# 42Motor_Control.net
KiCad netlist of a schematic drawn in Altium Designer
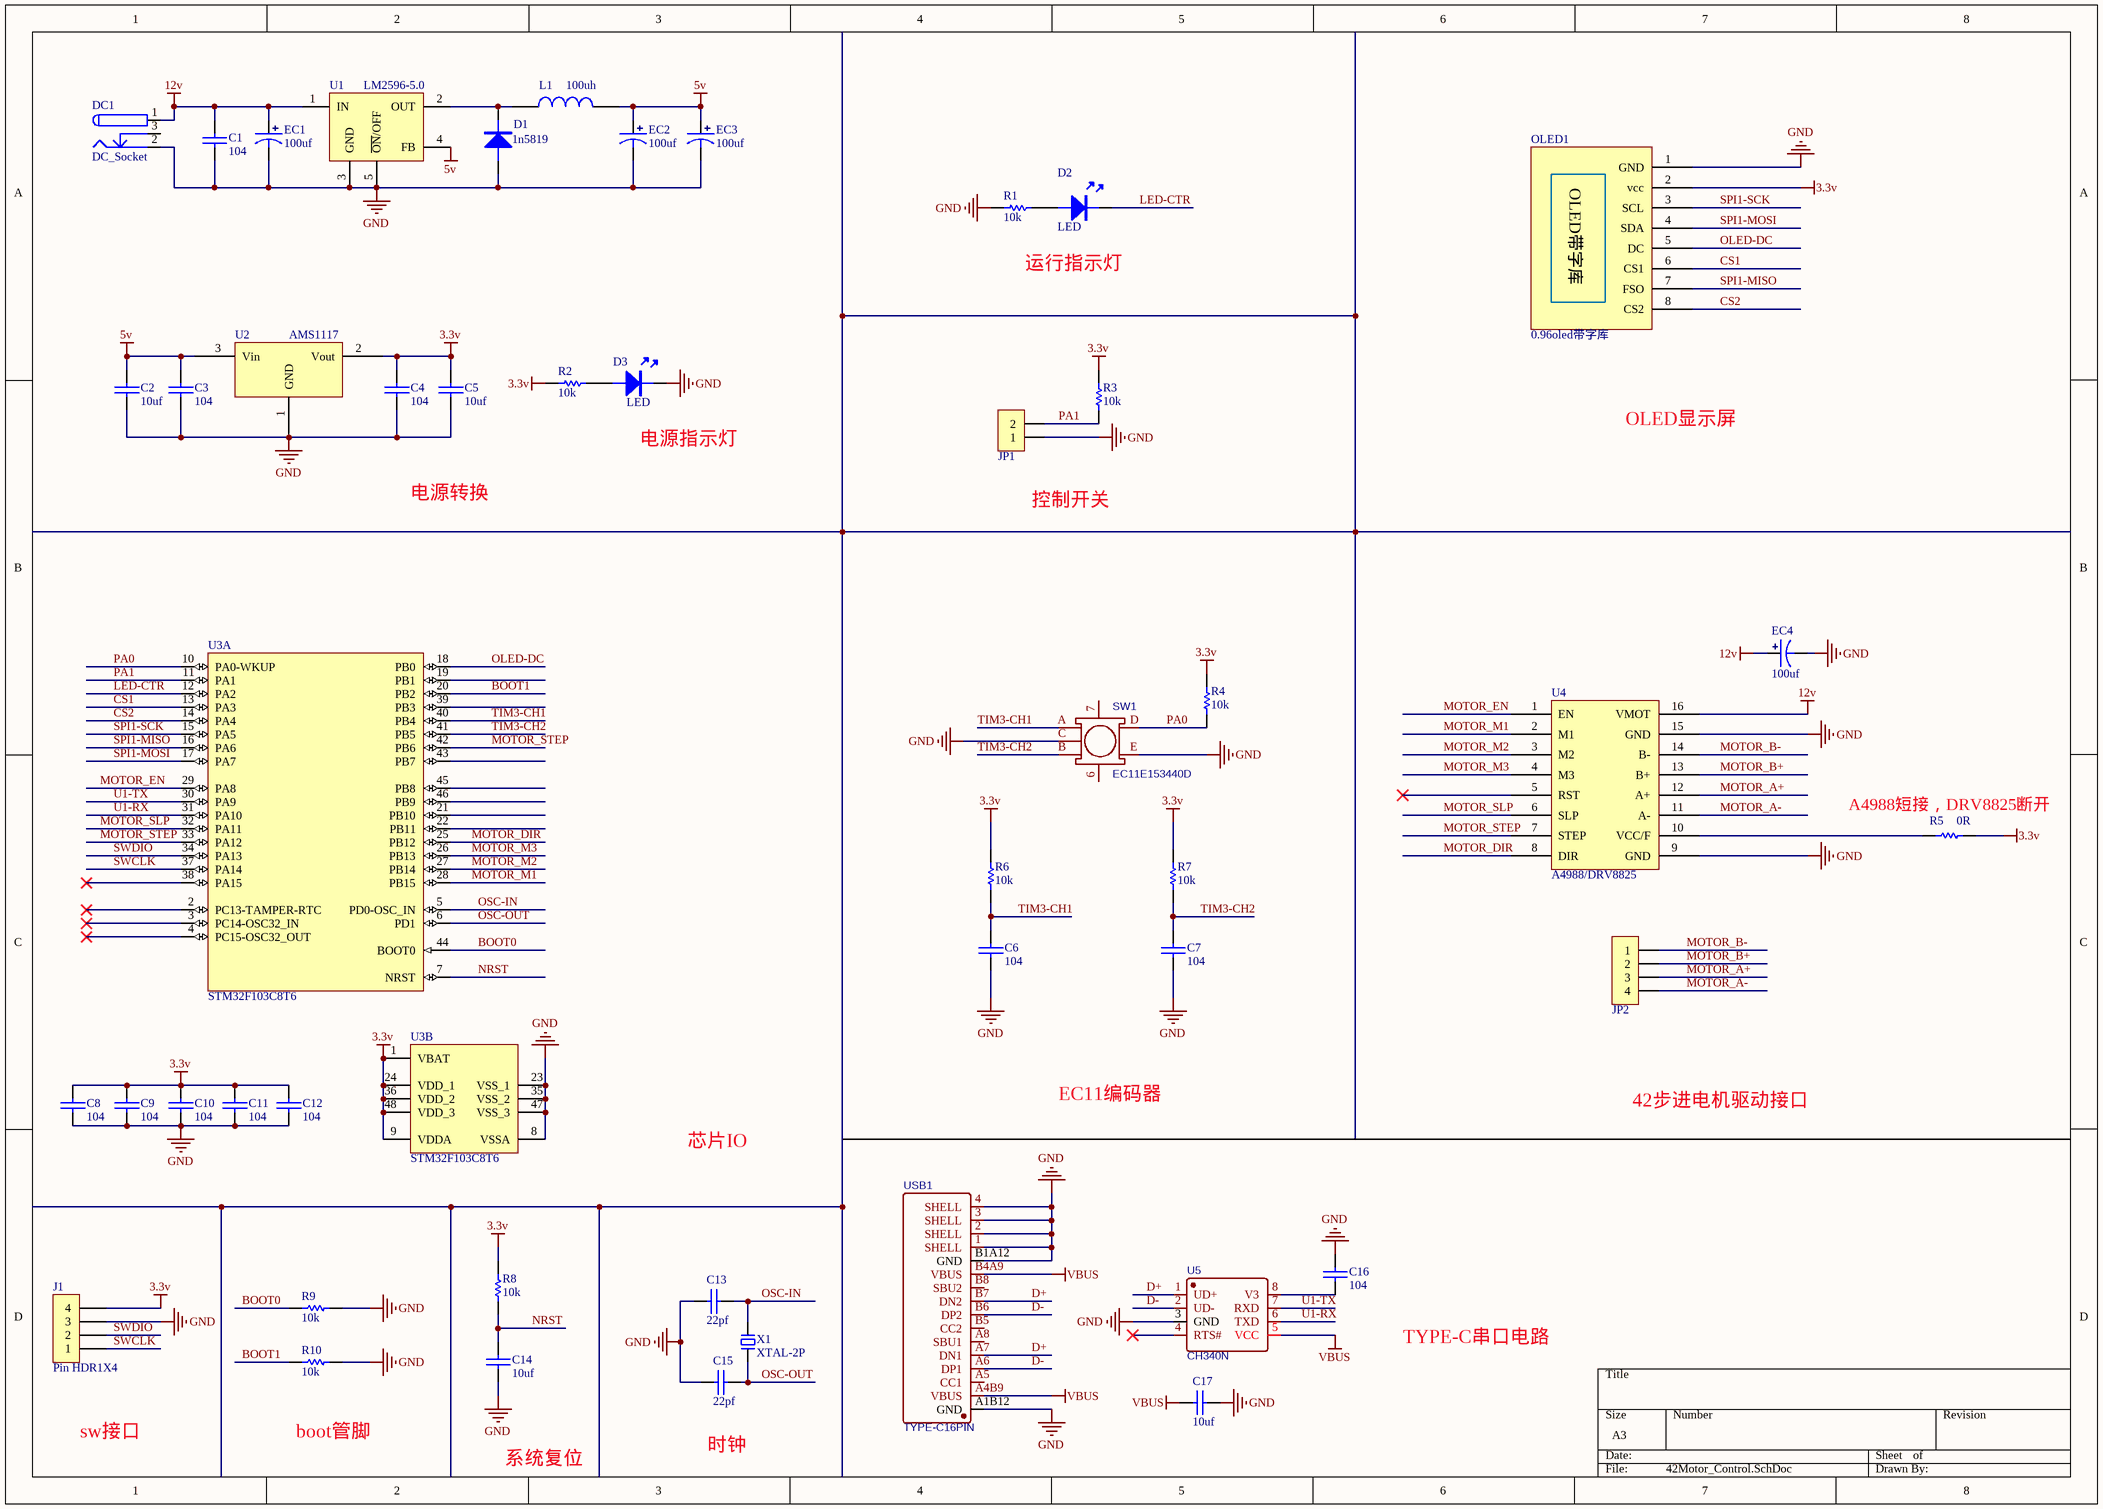
[diagram p0: 42Motor_Control.SchDoc]

(export (version "E")
  (design (tool "Eeschema 10.0.6"))
  (components
    (comp (ref "C1")
      (value "104")
      (footprint "0603C")
      (description "无极性电容")
      (libsource (lib "电容") (part "CAP"))
    )
    (comp (ref "C2")
      (value "10uf")
      (footprint "0603C")
      (description "无极性电容")
      (libsource (lib "电容") (part "CAP"))
    )
    (comp (ref "C3")
      (value "104")
      (footprint "0603C")
      (description "无极性电容")
      (libsource (lib "电容") (part "CAP"))
    )
    (comp (ref "C4")
      (value "104")
      (footprint "0603C")
      (description "无极性电容")
      (libsource (lib "电容") (part "CAP"))
    )
    (comp (ref "C5")
      (value "10uf")
      (footprint "0603C")
      (description "无极性电容")
      (libsource (lib "电容") (part "CAP"))
    )
    (comp (ref "C6")
      (value "104")
      (footprint "0603C")
      (description "无极性电容")
      (libsource (lib "电容") (part "CAP"))
    )
    (comp (ref "C7")
      (value "104")
      (footprint "0603C")
      (description "无极性电容")
      (libsource (lib "电容") (part "CAP"))
    )
    (comp (ref "C8")
      (value "104")
      (footprint "0603C")
      (description "无极性电容")
      (libsource (lib "电容") (part "CAP"))
    )
    (comp (ref "C9")
      (value "104")
      (footprint "0603C")
      (description "无极性电容")
      (libsource (lib "电容") (part "CAP"))
    )
    (comp (ref "C10")
      (value "104")
      (footprint "0603C")
      (description "无极性电容")
      (libsource (lib "电容") (part "CAP"))
    )
    (comp (ref "C11")
      (value "104")
      (footprint "0603C")
      (description "无极性电容")
      (libsource (lib "电容") (part "CAP"))
    )
    (comp (ref "C12")
      (value "104")
      (footprint "0603C")
      (description "无极性电容")
      (libsource (lib "电容") (part "CAP"))
    )
    (comp (ref "C13")
      (value "22pf")
      (footprint "0603C")
      (description "无极性电容")
      (libsource (lib "电容") (part "CAP"))
    )
    (comp (ref "C14")
      (value "10uf")
      (footprint "0603C")
      (description "无极性电容")
      (libsource (lib "电容") (part "CAP"))
    )
    (comp (ref "C15")
      (value "22pf")
      (footprint "0603C")
      (description "无极性电容")
      (libsource (lib "电容") (part "CAP"))
    )
    (comp (ref "C16")
      (value "104")
      (footprint "0603C")
      (description "无极性电容")
      (libsource (lib "电容") (part "CAP"))
    )
    (comp (ref "C17")
      (value "10uf")
      (footprint "0603C")
      (description "无极性电容")
      (libsource (lib "电容") (part "CAP"))
    )
    (comp (ref "D1")
      (value "1n5819")
      (footprint "SOD-323")
      (description "普通二极管")
      (libsource (lib "二极管") (part "DIODE"))
    )
    (comp (ref "D2") (value "LED") (footprint "LED-0603W") (libsource (lib "LED") (part "LED")))
    (comp (ref "D3") (value "LED") (footprint "LED-0603W") (libsource (lib "LED") (part "LED")))
    (comp (ref "DC1") (value "DC_Socket") (footprint "DC-050") (libsource (lib "电源插座") (part "DC_Socket")))
    (comp (ref "EC1")
      (value "100uf")
      (footprint "SMD-EC6.3X6.3X10")
      (description "贴片电解电容")
      (libsource (lib "电容") (part "SMD_ECAP"))
    )
    (comp (ref "EC2")
      (value "100uf")
      (footprint "SMD-EC6.3X6.3X10")
      (description "贴片电解电容")
      (libsource (lib "电容") (part "SMD_ECAP"))
    )
    (comp (ref "EC3")
      (value "100uf")
      (footprint "SMD-EC6.3X6.3X10")
      (description "贴片电解电容")
      (libsource (lib "电容") (part "SMD_ECAP"))
    )
    (comp (ref "EC4")
      (value "100uf")
      (footprint "SMD-EC6.3X6.3X10")
      (description "贴片电解电容")
      (libsource (lib "电容") (part "SMD_ECAP"))
    )
    (comp (ref "J1")
      (value "Pin HDR1X4")
      (footprint "Pin HDR1X4/2.54mm-S")
      (libsource (lib "排针") (part "Pin HDR1X4"))
    )
    (comp (ref "JP1")
      (value "HDR-1X2")
      (footprint "XH2.54-LI-2P")
      (description "2P接插件")
      (fields (field (name "版权归属") "封装库来自淘宝 ID：黄晶宝石"))
      (libsource (lib "5.3 - 接插件-脚距2.54 (100mil) ") (part "Header 2"))
    )
    (comp (ref "JP2")
      (value "HDR-1X4")
      (footprint "XH2.54-WI-4P")
      (description "4P接插件")
      (fields (field (name "版权归属") "封装库来自淘宝 ID：黄晶宝石"))
      (libsource (lib "5.3 - 接插件-脚距2.54 (100mil) ") (part "Header 4"))
    )
    (comp (ref "L1")
      (value "100uh")
      (footprint "CDRH74")
      (description "INDUCTOR")
      (libsource (lib "电感") (part "INDUCTOR"))
    )
    (comp (ref "OLED1")
      (value "0.96oled带字库")
      (footprint "中景园0.96带字库")
      (libsource (lib "42Motor_Control") (part "0.96oled带字库"))
    )
    (comp (ref "R1") (value "10k") (footprint "0603R") (libsource (lib "电阻") (part "RES")))
    (comp (ref "R2") (value "10k") (footprint "0603R") (libsource (lib "电阻") (part "RES")))
    (comp (ref "R3") (value "10k") (footprint "0603R") (libsource (lib "电阻") (part "RES")))
    (comp (ref "R4") (value "10k") (footprint "0603R") (libsource (lib "电阻") (part "RES")))
    (comp (ref "R5") (value "0R") (footprint "0603R") (libsource (lib "电阻") (part "RES")))
    (comp (ref "R6") (value "10k") (footprint "0603R") (libsource (lib "电阻") (part "RES")))
    (comp (ref "R7") (value "10k") (footprint "0603R") (libsource (lib "电阻") (part "RES")))
    (comp (ref "R8") (value "10k") (footprint "0603R") (libsource (lib "电阻") (part "RES")))
    (comp (ref "R9") (value "10k") (footprint "0603R") (libsource (lib "电阻") (part "RES")))
    (comp (ref "R10") (value "10k") (footprint "0603R") (libsource (lib "电阻") (part "RES")))
    (comp (ref "SW1")
      (value "EC11E153440D")
      (footprint "SW-TH_EC11XXXXXXXX")
      (fields (field (name "BOM_SUPPLIER PART") "C370992") (field (name "CONTRIBUTOR") "LCSC"))
      (libsource (lib "ec11") (part "EC11E153440D"))
    )
    (comp (ref "U1")
      (value "LM2596-5.0")
      (footprint "TO263-5A")
      (description "DC降压芯片")
      (libsource (lib "电源芯片") (part "LM2596-5.0"))
    )
    (comp (ref "U2")
      (value "AMS1117")
      (footprint "SOT223")
      (description "三端稳压芯片")
      (libsource (lib "电源芯片") (part "AMS1117"))
    )
    (comp (ref "U3")
      (value "STM32F103C8T6")
      (footprint "LQFP48_N")
      (libsource (lib "2.3 - STM32 F1系列MCU 集成库") (part "STM32F103C8T6"))
    )
    (comp (ref "U4")
      (value "A4988/DRV8825")
      (footprint "A4988/DRV8825")
      (libsource (lib "42Motor_Control") (part "A4988/DRV8825"))
    )
    (comp (ref "U5")
      (value "CH340N")
      (footprint "SOP-8_L4.9-W3.9-P1.27-LS6.0-BL")
      (fields (field (name "BOM_MANUFACTURER PART") "CH330N") (field (name "BOM_SUPPLIER PART") "C108996"))
      (libsource (lib "HM_Clock") (part "CH340N"))
    )
    (comp (ref "USB1")
      (value "TYPE-C16PIN")
      (footprint "USB-C-SMD_TYPE-C16PIN")
      (fields (field (name "BOM_SUPPLIER PART") "C393939") (field (name "CONTRIBUTOR") "LCSC"))
      (libsource (lib "HM_Clock") (part "TYPE-C16PIN"))
    )
    (comp (ref "X1")
      (value "XTAL-2P")
      (footprint "OSC HC-49SMD")
      (description "2脚无源脚晶振")
      (libsource (lib "晶振") (part "XTAL-2P"))
    )
  )
  (nets
    (net (code "1") (name "/BOOT0") (class "Default")
      (node (ref "R9") (pin "1") (pinfunction "1_1") (pintype "passive"))
      (node (ref "U3") (pin "44") (pinfunction "BOOT0_44") (pintype "input"))
    )
    (net (code "2") (name "/BOOT1") (class "Default")
      (node (ref "R10") (pin "1") (pinfunction "1_1") (pintype "passive"))
      (node (ref "U3") (pin "20") (pinfunction "PB2_20") (pintype "bidirectional"))
    )
    (net (code "3") (name "/CS1") (class "Default")
      (node (ref "OLED1") (pin "6") (pinfunction "CS1_6") (pintype "passive"))
      (node (ref "U3") (pin "13") (pinfunction "PA3_13") (pintype "bidirectional"))
    )
    (net (code "4") (name "/CS2") (class "Default")
      (node (ref "OLED1") (pin "8") (pinfunction "CS2_8") (pintype "passive"))
      (node (ref "U3") (pin "14") (pinfunction "PA4_14") (pintype "bidirectional"))
    )
    (net (code "5") (name "/D+") (class "Default")
      (node (ref "U5") (pin "1") (pinfunction "UD+_1") (pintype "passive"))
      (node (ref "USB1") (pin "A7") (pinfunction "DN1_A7") (pintype "passive"))
      (node (ref "USB1") (pin "B7") (pinfunction "DN2_B7") (pintype "passive"))
    )
    (net (code "6") (name "/D-") (class "Default")
      (node (ref "U5") (pin "2") (pinfunction "UD-_2") (pintype "passive"))
      (node (ref "USB1") (pin "A6") (pinfunction "DP1_A6") (pintype "passive"))
      (node (ref "USB1") (pin "B6") (pinfunction "DP2_B6") (pintype "passive"))
    )
    (net (code "7") (name "/LED-CTR") (class "Default")
      (node (ref "D2") (pin "K") (pinfunction "K_K") (pintype "passive"))
      (node (ref "U3") (pin "12") (pinfunction "PA2_12") (pintype "bidirectional"))
    )
    (net (code "8") (name "/MOTOR_A+") (class "Default")
      (node (ref "JP2") (pin "3") (pinfunction "3_3") (pintype "passive"))
      (node (ref "U4") (pin "12") (pinfunction "A+_12") (pintype "passive"))
    )
    (net (code "9") (name "/MOTOR_A-") (class "Default")
      (node (ref "JP2") (pin "4") (pinfunction "4_4") (pintype "passive"))
      (node (ref "U4") (pin "11") (pinfunction "A-_11") (pintype "passive"))
    )
    (net (code "10") (name "/MOTOR_B+") (class "Default")
      (node (ref "JP2") (pin "2") (pinfunction "2_2") (pintype "passive"))
      (node (ref "U4") (pin "13") (pinfunction "B+_13") (pintype "passive"))
    )
    (net (code "11") (name "/MOTOR_B-") (class "Default")
      (node (ref "JP2") (pin "1") (pinfunction "1_1") (pintype "passive"))
      (node (ref "U4") (pin "14") (pinfunction "B-_14") (pintype "passive"))
    )
    (net (code "12") (name "/MOTOR_DIR") (class "Default")
      (node (ref "U3") (pin "25") (pinfunction "PB12_25") (pintype "bidirectional"))
      (node (ref "U4") (pin "8") (pinfunction "DIR_8") (pintype "passive"))
    )
    (net (code "13") (name "/MOTOR_EN") (class "Default")
      (node (ref "U3") (pin "29") (pinfunction "PA8_29") (pintype "bidirectional"))
      (node (ref "U4") (pin "1") (pinfunction "EN_1") (pintype "passive"))
    )
    (net (code "14") (name "/MOTOR_M1") (class "Default")
      (node (ref "U3") (pin "28") (pinfunction "PB15_28") (pintype "bidirectional"))
      (node (ref "U4") (pin "2") (pinfunction "M1_2") (pintype "passive"))
    )
    (net (code "15") (name "/MOTOR_M2") (class "Default")
      (node (ref "U3") (pin "27") (pinfunction "PB14_27") (pintype "bidirectional"))
      (node (ref "U4") (pin "3") (pinfunction "M2_3") (pintype "passive"))
    )
    (net (code "16") (name "/MOTOR_M3") (class "Default")
      (node (ref "U3") (pin "26") (pinfunction "PB13_26") (pintype "bidirectional"))
      (node (ref "U4") (pin "4") (pinfunction "M3_4") (pintype "passive"))
    )
    (net (code "17") (name "/MOTOR_SLP") (class "Default")
      (node (ref "U3") (pin "32") (pinfunction "PA11_32") (pintype "bidirectional"))
      (node (ref "U4") (pin "6") (pinfunction "SLP_6") (pintype "passive"))
    )
    (net (code "18") (name "/MOTOR_STEP") (class "Default")
      (node (ref "U3") (pin "33") (pinfunction "PA12_33") (pintype "bidirectional"))
      (node (ref "U3") (pin "42") (pinfunction "PB6_42") (pintype "bidirectional"))
      (node (ref "U4") (pin "7") (pinfunction "STEP_7") (pintype "passive"))
    )
    (net (code "19") (name "/NRST") (class "Default")
      (node (ref "C14") (pin "2") (pinfunction "2_2") (pintype "passive"))
      (node (ref "R8") (pin "1") (pinfunction "1_1") (pintype "passive"))
      (node (ref "U3") (pin "7") (pinfunction "NRST_7") (pintype "bidirectional"))
    )
    (net (code "20") (name "/OLED-DC") (class "Default")
      (node (ref "OLED1") (pin "5") (pinfunction "DC_5") (pintype "passive"))
      (node (ref "U3") (pin "18") (pinfunction "PB0_18") (pintype "bidirectional"))
    )
    (net (code "21") (name "/OSC-IN") (class "Default")
      (node (ref "C13") (pin "2") (pinfunction "2_2") (pintype "passive"))
      (node (ref "U3") (pin "5") (pinfunction "PD0-OSC_IN_5") (pintype "bidirectional"))
      (node (ref "X1") (pin "1") (pinfunction "1_1") (pintype "passive"))
    )
    (net (code "22") (name "/OSC-OUT") (class "Default")
      (node (ref "C15") (pin "2") (pinfunction "2_2") (pintype "passive"))
      (node (ref "U3") (pin "6") (pinfunction "PD1_6") (pintype "bidirectional"))
      (node (ref "X1") (pin "2") (pinfunction "2_2") (pintype "passive"))
    )
    (net (code "23") (name "/PA0") (class "Default")
      (node (ref "R4") (pin "2") (pinfunction "2_2") (pintype "passive"))
      (node (ref "SW1") (pin "D") (pinfunction "D_D") (pintype "passive"))
      (node (ref "U3") (pin "10") (pinfunction "PA0-WKUP_10") (pintype "bidirectional"))
    )
    (net (code "24") (name "/PA1") (class "Default")
      (node (ref "JP1") (pin "2") (pinfunction "2_2") (pintype "passive"))
      (node (ref "R3") (pin "2") (pinfunction "2_2") (pintype "passive"))
      (node (ref "U3") (pin "11") (pinfunction "PA1_11") (pintype "bidirectional"))
    )
    (net (code "25") (name "/SPI1-MISO") (class "Default")
      (node (ref "OLED1") (pin "7") (pinfunction "FSO_7") (pintype "passive"))
      (node (ref "U3") (pin "16") (pinfunction "PA6_16") (pintype "bidirectional"))
    )
    (net (code "26") (name "/SPI1-MOSI") (class "Default")
      (node (ref "OLED1") (pin "4") (pinfunction "SDA_4") (pintype "passive"))
      (node (ref "U3") (pin "17") (pinfunction "PA7_17") (pintype "bidirectional"))
    )
    (net (code "27") (name "/SPI1-SCK") (class "Default")
      (node (ref "OLED1") (pin "3") (pinfunction "SCL_3") (pintype "passive"))
      (node (ref "U3") (pin "15") (pinfunction "PA5_15") (pintype "bidirectional"))
    )
    (net (code "28") (name "/SWCLK") (class "Default")
      (node (ref "J1") (pin "1") (pinfunction "1_1") (pintype "passive"))
      (node (ref "U3") (pin "37") (pinfunction "PA14_37") (pintype "bidirectional"))
    )
    (net (code "29") (name "/SWDIO") (class "Default")
      (node (ref "J1") (pin "2") (pinfunction "2_2") (pintype "passive"))
      (node (ref "U3") (pin "34") (pinfunction "PA13_34") (pintype "bidirectional"))
    )
    (net (code "30") (name "/TIM3-CH1") (class "Default")
      (node (ref "C6") (pin "1") (pinfunction "1_1") (pintype "passive"))
      (node (ref "R6") (pin "2") (pinfunction "2_2") (pintype "passive"))
      (node (ref "SW1") (pin "A") (pinfunction "A_A") (pintype "passive"))
      (node (ref "U3") (pin "40") (pinfunction "PB4_40") (pintype "bidirectional"))
    )
    (net (code "31") (name "/TIM3-CH2") (class "Default")
      (node (ref "C7") (pin "1") (pinfunction "1_1") (pintype "passive"))
      (node (ref "R7") (pin "2") (pinfunction "2_2") (pintype "passive"))
      (node (ref "SW1") (pin "B") (pinfunction "B_B") (pintype "passive"))
      (node (ref "U3") (pin "41") (pinfunction "PB5_41") (pintype "bidirectional"))
    )
    (net (code "32") (name "/U1-RX") (class "Default")
      (node (ref "U3") (pin "31") (pinfunction "PA10_31") (pintype "bidirectional"))
      (node (ref "U5") (pin "6") (pinfunction "TXD_6") (pintype "passive"))
    )
    (net (code "33") (name "/U1-TX") (class "Default")
      (node (ref "U3") (pin "30") (pinfunction "PA9_30") (pintype "bidirectional"))
      (node (ref "U5") (pin "7") (pinfunction "RXD_7") (pintype "passive"))
    )
    (net (code "34") (name "3.3v") (class "Default")
      (node (ref "C10") (pin "2") (pinfunction "2_2") (pintype "passive"))
      (node (ref "C11") (pin "2") (pinfunction "2_2") (pintype "passive"))
      (node (ref "C12") (pin "2") (pinfunction "2_2") (pintype "passive"))
      (node (ref "C4") (pin "2") (pinfunction "2_2") (pintype "passive"))
      (node (ref "C5") (pin "2") (pinfunction "2_2") (pintype "passive"))
      (node (ref "C8") (pin "2") (pinfunction "2_2") (pintype "passive"))
      (node (ref "C9") (pin "2") (pinfunction "2_2") (pintype "passive"))
      (node (ref "J1") (pin "4") (pinfunction "4_4") (pintype "passive"))
      (node (ref "OLED1") (pin "2") (pinfunction "vcc_2") (pintype "passive"))
      (node (ref "R2") (pin "2") (pinfunction "2_2") (pintype "passive"))
      (node (ref "R3") (pin "1") (pinfunction "1_1") (pintype "passive"))
      (node (ref "R4") (pin "1") (pinfunction "1_1") (pintype "passive"))
      (node (ref "R5") (pin "1") (pinfunction "1_1") (pintype "passive"))
      (node (ref "R6") (pin "1") (pinfunction "1_1") (pintype "passive"))
      (node (ref "R7") (pin "1") (pinfunction "1_1") (pintype "passive"))
      (node (ref "R8") (pin "2") (pinfunction "2_2") (pintype "passive"))
      (node (ref "U2") (pin "2") (pinfunction "Vout_2") (pintype "passive"))
      (node (ref "U3") (pin "1") (pinfunction "VBAT_1") (pintype "power_in"))
      (node (ref "U3") (pin "24") (pinfunction "VDD_1_24") (pintype "power_in"))
      (node (ref "U3") (pin "36") (pinfunction "VDD_2_36") (pintype "power_in"))
      (node (ref "U3") (pin "48") (pinfunction "VDD_3_48") (pintype "power_in"))
      (node (ref "U3") (pin "9") (pinfunction "VDDA_9") (pintype "power_in"))
    )
    (net (code "35") (name "5v") (class "Default")
      (node (ref "C2") (pin "2") (pinfunction "2_2") (pintype "passive"))
      (node (ref "C3") (pin "2") (pinfunction "2_2") (pintype "passive"))
      (node (ref "EC2") (pin "1") (pinfunction "1_1") (pintype "passive"))
      (node (ref "EC3") (pin "1") (pinfunction "1_1") (pintype "passive"))
      (node (ref "L1") (pin "2") (pinfunction "2_2") (pintype "passive"))
      (node (ref "U1") (pin "4") (pinfunction "FB_4") (pintype "passive"))
      (node (ref "U2") (pin "3") (pinfunction "Vin_3") (pintype "passive"))
    )
    (net (code "36") (name "12v") (class "Default")
      (node (ref "C1") (pin "2") (pinfunction "2_2") (pintype "passive"))
      (node (ref "DC1") (pin "1") (pinfunction "1_1") (pintype "power_in"))
      (node (ref "EC1") (pin "1") (pinfunction "1_1") (pintype "passive"))
      (node (ref "EC4") (pin "1") (pinfunction "1_1") (pintype "passive"))
      (node (ref "U1") (pin "1") (pinfunction "IN_1") (pintype "power_in"))
      (node (ref "U4") (pin "16") (pinfunction "VMOT_16") (pintype "passive"))
    )
    (net (code "37") (name "GND") (class "Default")
      (node (ref "C1") (pin "1") (pinfunction "1_1") (pintype "passive"))
      (node (ref "C10") (pin "1") (pinfunction "1_1") (pintype "passive"))
      (node (ref "C11") (pin "1") (pinfunction "1_1") (pintype "passive"))
      (node (ref "C12") (pin "1") (pinfunction "1_1") (pintype "passive"))
      (node (ref "C13") (pin "1") (pinfunction "1_1") (pintype "passive"))
      (node (ref "C14") (pin "1") (pinfunction "1_1") (pintype "passive"))
      (node (ref "C15") (pin "1") (pinfunction "1_1") (pintype "passive"))
      (node (ref "C16") (pin "2") (pinfunction "2_2") (pintype "passive"))
      (node (ref "C17") (pin "2") (pinfunction "2_2") (pintype "passive"))
      (node (ref "C2") (pin "1") (pinfunction "1_1") (pintype "passive"))
      (node (ref "C3") (pin "1") (pinfunction "1_1") (pintype "passive"))
      (node (ref "C4") (pin "1") (pinfunction "1_1") (pintype "passive"))
      (node (ref "C5") (pin "1") (pinfunction "1_1") (pintype "passive"))
      (node (ref "C6") (pin "2") (pinfunction "2_2") (pintype "passive"))
      (node (ref "C7") (pin "2") (pinfunction "2_2") (pintype "passive"))
      (node (ref "C8") (pin "1") (pinfunction "1_1") (pintype "passive"))
      (node (ref "C9") (pin "1") (pinfunction "1_1") (pintype "passive"))
      (node (ref "D1") (pin "A") (pinfunction "A_A") (pintype "passive"))
      (node (ref "D3") (pin "K") (pinfunction "K_K") (pintype "passive"))
      (node (ref "DC1") (pin "2") (pinfunction "2_2") (pintype "power_in"))
      (node (ref "EC1") (pin "2") (pinfunction "2_2") (pintype "passive"))
      (node (ref "EC2") (pin "2") (pinfunction "2_2") (pintype "passive"))
      (node (ref "EC3") (pin "2") (pinfunction "2_2") (pintype "passive"))
      (node (ref "EC4") (pin "2") (pinfunction "2_2") (pintype "passive"))
      (node (ref "J1") (pin "3") (pinfunction "3_3") (pintype "passive"))
      (node (ref "JP1") (pin "1") (pinfunction "1_1") (pintype "passive"))
      (node (ref "OLED1") (pin "1") (pinfunction "GND_1") (pintype "passive"))
      (node (ref "R1") (pin "2") (pinfunction "2_2") (pintype "passive"))
      (node (ref "R10") (pin "2") (pinfunction "2_2") (pintype "passive"))
      (node (ref "R9") (pin "2") (pinfunction "2_2") (pintype "passive"))
      (node (ref "SW1") (pin "C") (pinfunction "C_C") (pintype "passive"))
      (node (ref "SW1") (pin "E") (pinfunction "E_E") (pintype "passive"))
      (node (ref "U1") (pin "3") (pinfunction "GND_3") (pintype "power_in"))
      (node (ref "U1") (pin "5") (pinfunction "~{ON}/OFF_5") (pintype "passive"))
      (node (ref "U2") (pin "1") (pinfunction "GND_1") (pintype "passive"))
      (node (ref "U3") (pin "23") (pinfunction "VSS_1_23") (pintype "power_in"))
      (node (ref "U3") (pin "35") (pinfunction "VSS_2_35") (pintype "power_in"))
      (node (ref "U3") (pin "47") (pinfunction "VSS_3_47") (pintype "power_in"))
      (node (ref "U3") (pin "8") (pinfunction "VSSA_8") (pintype "power_in"))
      (node (ref "U4") (pin "15") (pinfunction "GND_15") (pintype "passive"))
      (node (ref "U4") (pin "9") (pinfunction "GND_9") (pintype "passive"))
      (node (ref "U5") (pin "3") (pinfunction "GND_3") (pintype "passive"))
      (node (ref "USB1") (pin "1") (pinfunction "SHELL_1") (pintype "passive"))
      (node (ref "USB1") (pin "2") (pinfunction "SHELL_2") (pintype "passive"))
      (node (ref "USB1") (pin "3") (pinfunction "SHELL_3") (pintype "passive"))
      (node (ref "USB1") (pin "4") (pinfunction "SHELL_4") (pintype "passive"))
      (node (ref "USB1") (pin "A1B12") (pinfunction "GND_A1B12") (pintype "passive"))
      (node (ref "USB1") (pin "B1A12") (pinfunction "GND_B1A12") (pintype "passive"))
    )
    (net (code "38") (name "Net-(D2-PadA)") (class "Default")
      (node (ref "D2") (pin "A") (pinfunction "A_A") (pintype "passive"))
      (node (ref "R1") (pin "1") (pinfunction "1_1") (pintype "passive"))
    )
    (net (code "39") (name "Net-(D3-PadA)") (class "Default")
      (node (ref "D3") (pin "A") (pinfunction "A_A") (pintype "passive"))
      (node (ref "R2") (pin "1") (pinfunction "1_1") (pintype "passive"))
    )
    (net (code "40") (name "Net-(U1-OUT)") (class "Default")
      (node (ref "D1") (pin "K") (pinfunction "K_K") (pintype "passive"))
      (node (ref "L1") (pin "1") (pinfunction "1_1") (pintype "passive"))
      (node (ref "U1") (pin "2") (pinfunction "OUT_2") (pintype "power_in"))
    )
    (net (code "41") (name "Net-(U4-VCC{slash}F)") (class "Default")
      (node (ref "R5") (pin "2") (pinfunction "2_2") (pintype "passive"))
      (node (ref "U4") (pin "10") (pinfunction "VCC/F_10") (pintype "passive"))
    )
    (net (code "42") (name "Net-(U5-V3)") (class "Default")
      (node (ref "C16") (pin "1") (pinfunction "1_1") (pintype "passive"))
      (node (ref "U5") (pin "8") (pinfunction "V3_8") (pintype "passive"))
    )
    (net (code "43") (name "VBUS") (class "Default")
      (node (ref "C17") (pin "1") (pinfunction "1_1") (pintype "passive"))
      (node (ref "U5") (pin "5") (pinfunction "VCC_5") (pintype "passive"))
      (node (ref "USB1") (pin "A4B9") (pinfunction "VBUS_A4B9") (pintype "passive"))
      (node (ref "USB1") (pin "B4A9") (pinfunction "VBUS_B4A9") (pintype "passive"))
    )
    (net (code "44") (name "unconnected-(DC1-Pad3)") (class "Default")
      (node (ref "DC1") (pin "3") (pinfunction "3_3") (pintype "power_in"))
    )
    (net (code "45") (name "unconnected-(SW1-Pad6)") (class "Default")
      (node (ref "SW1") (pin "6") (pinfunction "6_6") (pintype "passive"))
    )
    (net (code "46") (name "unconnected-(SW1-Pad7)") (class "Default")
      (node (ref "SW1") (pin "7") (pinfunction "7_7") (pintype "passive"))
    )
    (net (code "47") (name "unconnected-(U3A-PA15-Pad38)") (class "Default")
      (node (ref "U3") (pin "38") (pinfunction "PA15_38") (pintype "bidirectional+no_connect"))
    )
    (net (code "48") (name "unconnected-(U3A-PB1-Pad19)") (class "Default")
      (node (ref "U3") (pin "19") (pinfunction "PB1_19") (pintype "bidirectional"))
    )
    (net (code "49") (name "unconnected-(U3A-PB3-Pad39)") (class "Default")
      (node (ref "U3") (pin "39") (pinfunction "PB3_39") (pintype "bidirectional"))
    )
    (net (code "50") (name "unconnected-(U3A-PB7-Pad43)") (class "Default")
      (node (ref "U3") (pin "43") (pinfunction "PB7_43") (pintype "bidirectional"))
    )
    (net (code "51") (name "unconnected-(U3A-PB8-Pad45)") (class "Default")
      (node (ref "U3") (pin "45") (pinfunction "PB8_45") (pintype "bidirectional"))
    )
    (net (code "52") (name "unconnected-(U3A-PB9-Pad46)") (class "Default")
      (node (ref "U3") (pin "46") (pinfunction "PB9_46") (pintype "bidirectional"))
    )
    (net (code "53") (name "unconnected-(U3A-PB10-Pad21)") (class "Default")
      (node (ref "U3") (pin "21") (pinfunction "PB10_21") (pintype "bidirectional"))
    )
    (net (code "54") (name "unconnected-(U3A-PB11-Pad22)") (class "Default")
      (node (ref "U3") (pin "22") (pinfunction "PB11_22") (pintype "bidirectional"))
    )
    (net (code "55") (name "unconnected-(U3A-PC13-TAMPER-RTC-Pad2)") (class "Default")
      (node (ref "U3") (pin "2") (pinfunction "PC13-TAMPER-RTC_2") (pintype "bidirectional+no_connect"))
    )
    (net (code "56") (name "unconnected-(U3A-PC14-OSC32_IN-Pad3)") (class "Default")
      (node (ref "U3") (pin "3") (pinfunction "PC14-OSC32_IN_3") (pintype "bidirectional+no_connect"))
    )
    (net (code "57") (name "unconnected-(U3A-PC15-OSC32_OUT-Pad4)") (class "Default")
      (node (ref "U3") (pin "4") (pinfunction "PC15-OSC32_OUT_4") (pintype "bidirectional+no_connect"))
    )
    (net (code "58") (name "unconnected-(U4-RST-Pad5)") (class "Default")
      (node (ref "U4") (pin "5") (pinfunction "RST_5") (pintype "passive+no_connect"))
    )
    (net (code "59") (name "unconnected-(U5-RTS#-Pad4)") (class "Default")
      (node (ref "U5") (pin "4") (pinfunction "RTS#_4") (pintype "passive+no_connect"))
    )
    (net (code "60") (name "unconnected-(USB1-CC1-PadA5)") (class "Default")
      (node (ref "USB1") (pin "A5") (pinfunction "CC1_A5") (pintype "passive"))
    )
    (net (code "61") (name "unconnected-(USB1-CC2-PadB5)") (class "Default")
      (node (ref "USB1") (pin "B5") (pinfunction "CC2_B5") (pintype "passive"))
    )
    (net (code "62") (name "unconnected-(USB1-SBU1-PadA8)") (class "Default")
      (node (ref "USB1") (pin "A8") (pinfunction "SBU1_A8") (pintype "passive"))
    )
    (net (code "63") (name "unconnected-(USB1-SBU2-PadB8)") (class "Default")
      (node (ref "USB1") (pin "B8") (pinfunction "SBU2_B8") (pintype "passive"))
    )
  )
)
